# ozongenerator_regulator_ver_0_0_0_date_2.net
KiCad netlist of a schematic drawn in EAGLE
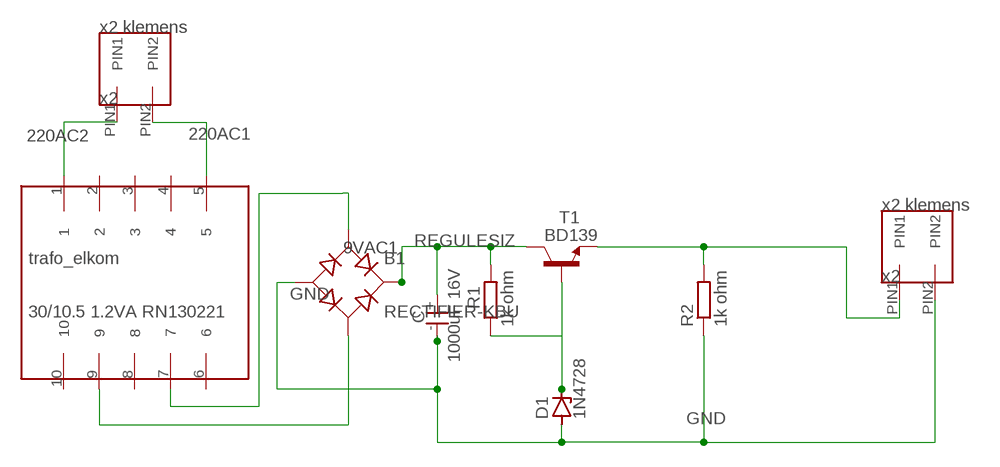
[diagram p0: schematic, sheet 1]

(export (version "E")
  (design (tool "Eeschema 10.0.6"))
  (components
    (comp (ref "B1")
      (value "RECTIFIER-KBU")
      (footprint "eagle-import:KBU")
      (libsource (lib "eagle-import") (part "RECTIFIER-KBU"))
    )
    (comp (ref "D1")
      (value "1N4728")
      (footprint "eagle-import:DO41Z10")
      (libsource (lib "eagle-import") (part "1N4728"))
    )
    (comp (ref "R1")
      (value "1k ohm")
      (footprint "eagle-import:0207_12")
      (libsource (lib "eagle-import") (part "R-EU_0207/12"))
    )
    (comp (ref "R2")
      (value "1k ohm")
      (footprint "eagle-import:0207_12")
      (libsource (lib "eagle-import") (part "R-EU_0207/12"))
    )
    (comp (ref "T1")
      (value "BD139")
      (footprint "eagle-import:TO126")
      (libsource (lib "eagle-import") (part "BD139"))
    )
    (comp (ref "U$1")
      (value "X2_KLEMENS")
      (footprint "eagle-import:X2_KLEMENS")
      (libsource (lib "eagle-import") (part "X2_KLEMENS"))
    )
    (comp (ref "U$2")
      (value "EL_KOM_TRAFO")
      (footprint "eagle-import:EL_KOM_TRAFO")
      (libsource (lib "eagle-import") (part "EL_KOM_TRAFO"))
    )
    (comp (ref "U$3")
      (value "CAPACITOR")
      (footprint "eagle-import:CAPACITOR")
      (libsource (lib "eagle-import") (part "CAPACITOR"))
    )
    (comp (ref "U$4")
      (value "X2_KLEMENS")
      (footprint "eagle-import:X2_KLEMENS")
      (libsource (lib "eagle-import") (part "X2_KLEMENS"))
    )
  )
  (nets
    (net (code "1") (name "/9VAC1") (class "Default")
      (node (ref "B1") (pin "AC1") (pinfunction "AC1_AC1") (pintype "passive"))
      (node (ref "U$2") (pin "7") (pinfunction "7_7") (pintype "bidirectional"))
    )
    (net (code "2") (name "/220AC1") (class "Default")
      (node (ref "U$1") (pin "PIN2") (pinfunction "PIN2_PIN2") (pintype "bidirectional"))
      (node (ref "U$2") (pin "5") (pinfunction "5_5") (pintype "bidirectional"))
    )
    (net (code "3") (name "/220AC2") (class "Default")
      (node (ref "U$1") (pin "PIN1") (pinfunction "PIN1_PIN1") (pintype "bidirectional"))
      (node (ref "U$2") (pin "1") (pinfunction "1_1") (pintype "bidirectional"))
    )
    (net (code "4") (name "/GND") (class "Default")
      (node (ref "B1") (pin "-") (pinfunction "-_-") (pintype "passive"))
      (node (ref "D1") (pin "A") (pinfunction "A_A") (pintype "passive"))
      (node (ref "R2") (pin "1") (pinfunction "1_1") (pintype "passive"))
      (node (ref "U$3") (pin "-") (pinfunction "-_-") (pintype "passive"))
      (node (ref "U$4") (pin "PIN2") (pinfunction "PIN2_PIN2") (pintype "bidirectional"))
    )
    (net (code "5") (name "/REGULESIZ") (class "Default")
      (node (ref "B1") (pin "+") (pinfunction "+_+") (pintype "passive"))
      (node (ref "R1") (pin "2") (pinfunction "2_2") (pintype "passive"))
      (node (ref "T1") (pin "2") (pinfunction "C_2") (pintype "passive"))
      (node (ref "U$3") (pin "+") (pinfunction "+_+") (pintype "bidirectional"))
    )
    (net (code "6") (name "Net-(B1-PadAC2)") (class "Default")
      (node (ref "B1") (pin "AC2") (pinfunction "AC2_AC2") (pintype "passive"))
      (node (ref "U$2") (pin "9") (pinfunction "9_9") (pintype "bidirectional"))
    )
    (net (code "7") (name "Net-(T1-B)") (class "Default")
      (node (ref "D1") (pin "C") (pinfunction "C_C") (pintype "passive"))
      (node (ref "R1") (pin "1") (pinfunction "1_1") (pintype "passive"))
      (node (ref "T1") (pin "3") (pinfunction "B_3") (pintype "passive"))
    )
    (net (code "8") (name "Net-(T1-E)") (class "Default")
      (node (ref "R2") (pin "2") (pinfunction "2_2") (pintype "passive"))
      (node (ref "T1") (pin "1") (pinfunction "E_1") (pintype "passive"))
      (node (ref "U$4") (pin "PIN1") (pinfunction "PIN1_PIN1") (pintype "bidirectional"))
    )
    (net (code "9") (name "unconnected-(U$2-Pad2)") (class "Default")
      (node (ref "U$2") (pin "2") (pinfunction "2_2") (pintype "bidirectional"))
    )
    (net (code "10") (name "unconnected-(U$2-Pad3)") (class "Default")
      (node (ref "U$2") (pin "3") (pinfunction "3_3") (pintype "bidirectional"))
    )
    (net (code "11") (name "unconnected-(U$2-Pad4)") (class "Default")
      (node (ref "U$2") (pin "4") (pinfunction "4_4") (pintype "bidirectional"))
    )
    (net (code "12") (name "unconnected-(U$2-Pad6)") (class "Default")
      (node (ref "U$2") (pin "6") (pinfunction "6_6") (pintype "bidirectional"))
    )
    (net (code "13") (name "unconnected-(U$2-Pad8)") (class "Default")
      (node (ref "U$2") (pin "8") (pinfunction "8_8") (pintype "bidirectional"))
    )
    (net (code "14") (name "unconnected-(U$2-Pad10)") (class "Default")
      (node (ref "U$2") (pin "10") (pinfunction "10_10") (pintype "bidirectional"))
    )
  )
)
